# drv.net
KiCad netlist of a schematic drawn in Altium Designer
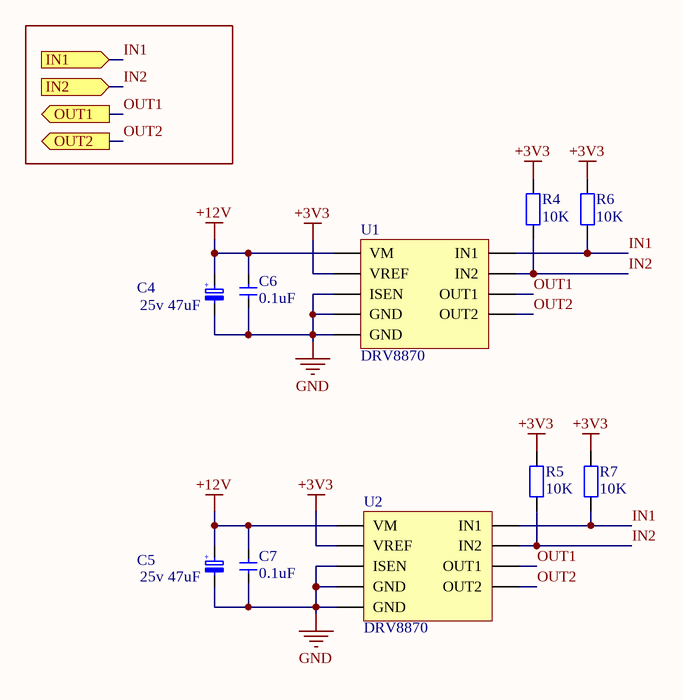
[diagram p0: drv.SchDoc]

(export (version "E")
  (design (tool "Eeschema 10.0.6"))
  (components
    (comp (ref "C4")
      (value "25v 47uF")
      (footprint "CAP_TANT_D")
      (description "Tantal SMD Cap")
      (libsource (lib "Asterisk") (part "CAP Tantal"))
    )
    (comp (ref "C5")
      (value "25v 47uF")
      (footprint "CAP_TANT_D")
      (description "Tantal SMD Cap")
      (libsource (lib "Asterisk") (part "CAP Tantal"))
    )
    (comp (ref "C6")
      (value "0.1uF")
      (footprint "CAP0805")
      (description "Ceramic SMD Cap")
      (libsource (lib "Asterisk") (part "CAP Ceramic"))
    )
    (comp (ref "C7")
      (value "0.1uF")
      (footprint "CAP0805")
      (description "Ceramic SMD Cap")
      (libsource (lib "Asterisk") (part "CAP Ceramic"))
    )
    (comp (ref "R4")
      (value "10K")
      (footprint "RES0805")
      (description "RES smd")
      (libsource (lib "Asterisk") (part "RES"))
    )
    (comp (ref "R5")
      (value "10K")
      (footprint "RES0805")
      (description "RES smd")
      (libsource (lib "Asterisk") (part "RES"))
    )
    (comp (ref "R6")
      (value "10K")
      (footprint "RES0805")
      (description "RES smd")
      (libsource (lib "Asterisk") (part "RES"))
    )
    (comp (ref "R7")
      (value "10K")
      (footprint "RES0805")
      (description "RES smd")
      (libsource (lib "Asterisk") (part "RES"))
    )
    (comp (ref "U1")
      (value "DRV8870")
      (footprint "HSOP-8")
      (description "DC motor driver 3.6A")
      (libsource (lib "Asterisk") (part "DRV8870"))
    )
    (comp (ref "U2")
      (value "DRV8870")
      (footprint "HSOP-8")
      (description "DC motor driver 3.6A")
      (libsource (lib "Asterisk") (part "DRV8870"))
    )
  )
  (nets
    (net (code "1") (name "+3V3") (class "Default")
      (node (ref "R4") (pin "2") (pinfunction "2_2") (pintype "passive"))
      (node (ref "R5") (pin "2") (pinfunction "2_2") (pintype "passive"))
      (node (ref "R6") (pin "2") (pinfunction "2_2") (pintype "passive"))
      (node (ref "R7") (pin "2") (pinfunction "2_2") (pintype "passive"))
      (node (ref "U1") (pin "4") (pinfunction "VREF_4") (pintype "passive"))
      (node (ref "U2") (pin "4") (pinfunction "VREF_4") (pintype "passive"))
    )
    (net (code "2") (name "+12V") (class "Default")
      (node (ref "C4") (pin "2") (pinfunction "PLUS_2") (pintype "passive"))
      (node (ref "C5") (pin "2") (pinfunction "PLUS_2") (pintype "passive"))
      (node (ref "C6") (pin "2") (pinfunction "2_2") (pintype "passive"))
      (node (ref "C7") (pin "2") (pinfunction "2_2") (pintype "passive"))
      (node (ref "U1") (pin "5") (pinfunction "VM_5") (pintype "passive"))
      (node (ref "U2") (pin "5") (pinfunction "VM_5") (pintype "passive"))
    )
    (net (code "3") (name "/IN1") (class "Default")
      (node (ref "R6") (pin "1") (pinfunction "1_1") (pintype "passive"))
      (node (ref "R7") (pin "1") (pinfunction "1_1") (pintype "passive"))
      (node (ref "U1") (pin "2") (pinfunction "IN1_2") (pintype "passive"))
      (node (ref "U2") (pin "2") (pinfunction "IN1_2") (pintype "passive"))
    )
    (net (code "4") (name "/IN2") (class "Default")
      (node (ref "R4") (pin "1") (pinfunction "1_1") (pintype "passive"))
      (node (ref "R5") (pin "1") (pinfunction "1_1") (pintype "passive"))
      (node (ref "U1") (pin "3") (pinfunction "IN2_3") (pintype "passive"))
      (node (ref "U2") (pin "3") (pinfunction "IN2_3") (pintype "passive"))
    )
    (net (code "5") (name "/OUT1") (class "Default")
      (node (ref "U1") (pin "6") (pinfunction "OUT1_6") (pintype "passive"))
      (node (ref "U2") (pin "6") (pinfunction "OUT1_6") (pintype "passive"))
    )
    (net (code "6") (name "/OUT2") (class "Default")
      (node (ref "U1") (pin "8") (pinfunction "OUT2_8") (pintype "passive"))
      (node (ref "U2") (pin "8") (pinfunction "OUT2_8") (pintype "passive"))
    )
    (net (code "7") (name "GND") (class "Default")
      (node (ref "C4") (pin "1") (pinfunction "MINUS_1") (pintype "passive"))
      (node (ref "C5") (pin "1") (pinfunction "MINUS_1") (pintype "passive"))
      (node (ref "C6") (pin "1") (pinfunction "1_1") (pintype "passive"))
      (node (ref "C7") (pin "1") (pinfunction "1_1") (pintype "passive"))
      (node (ref "U1") (pin "1") (pinfunction "GND_1") (pintype "passive"))
      (node (ref "U1") (pin "7") (pinfunction "ISEN_7") (pintype "passive"))
      (node (ref "U1") (pin "9") (pinfunction "GND_9") (pintype "passive"))
      (node (ref "U2") (pin "1") (pinfunction "GND_1") (pintype "passive"))
      (node (ref "U2") (pin "7") (pinfunction "ISEN_7") (pintype "passive"))
      (node (ref "U2") (pin "9") (pinfunction "GND_9") (pintype "passive"))
    )
  )
)
